# NT_SolarModule_filterfinder.net
KiCad netlist of a schematic drawn in EAGLE
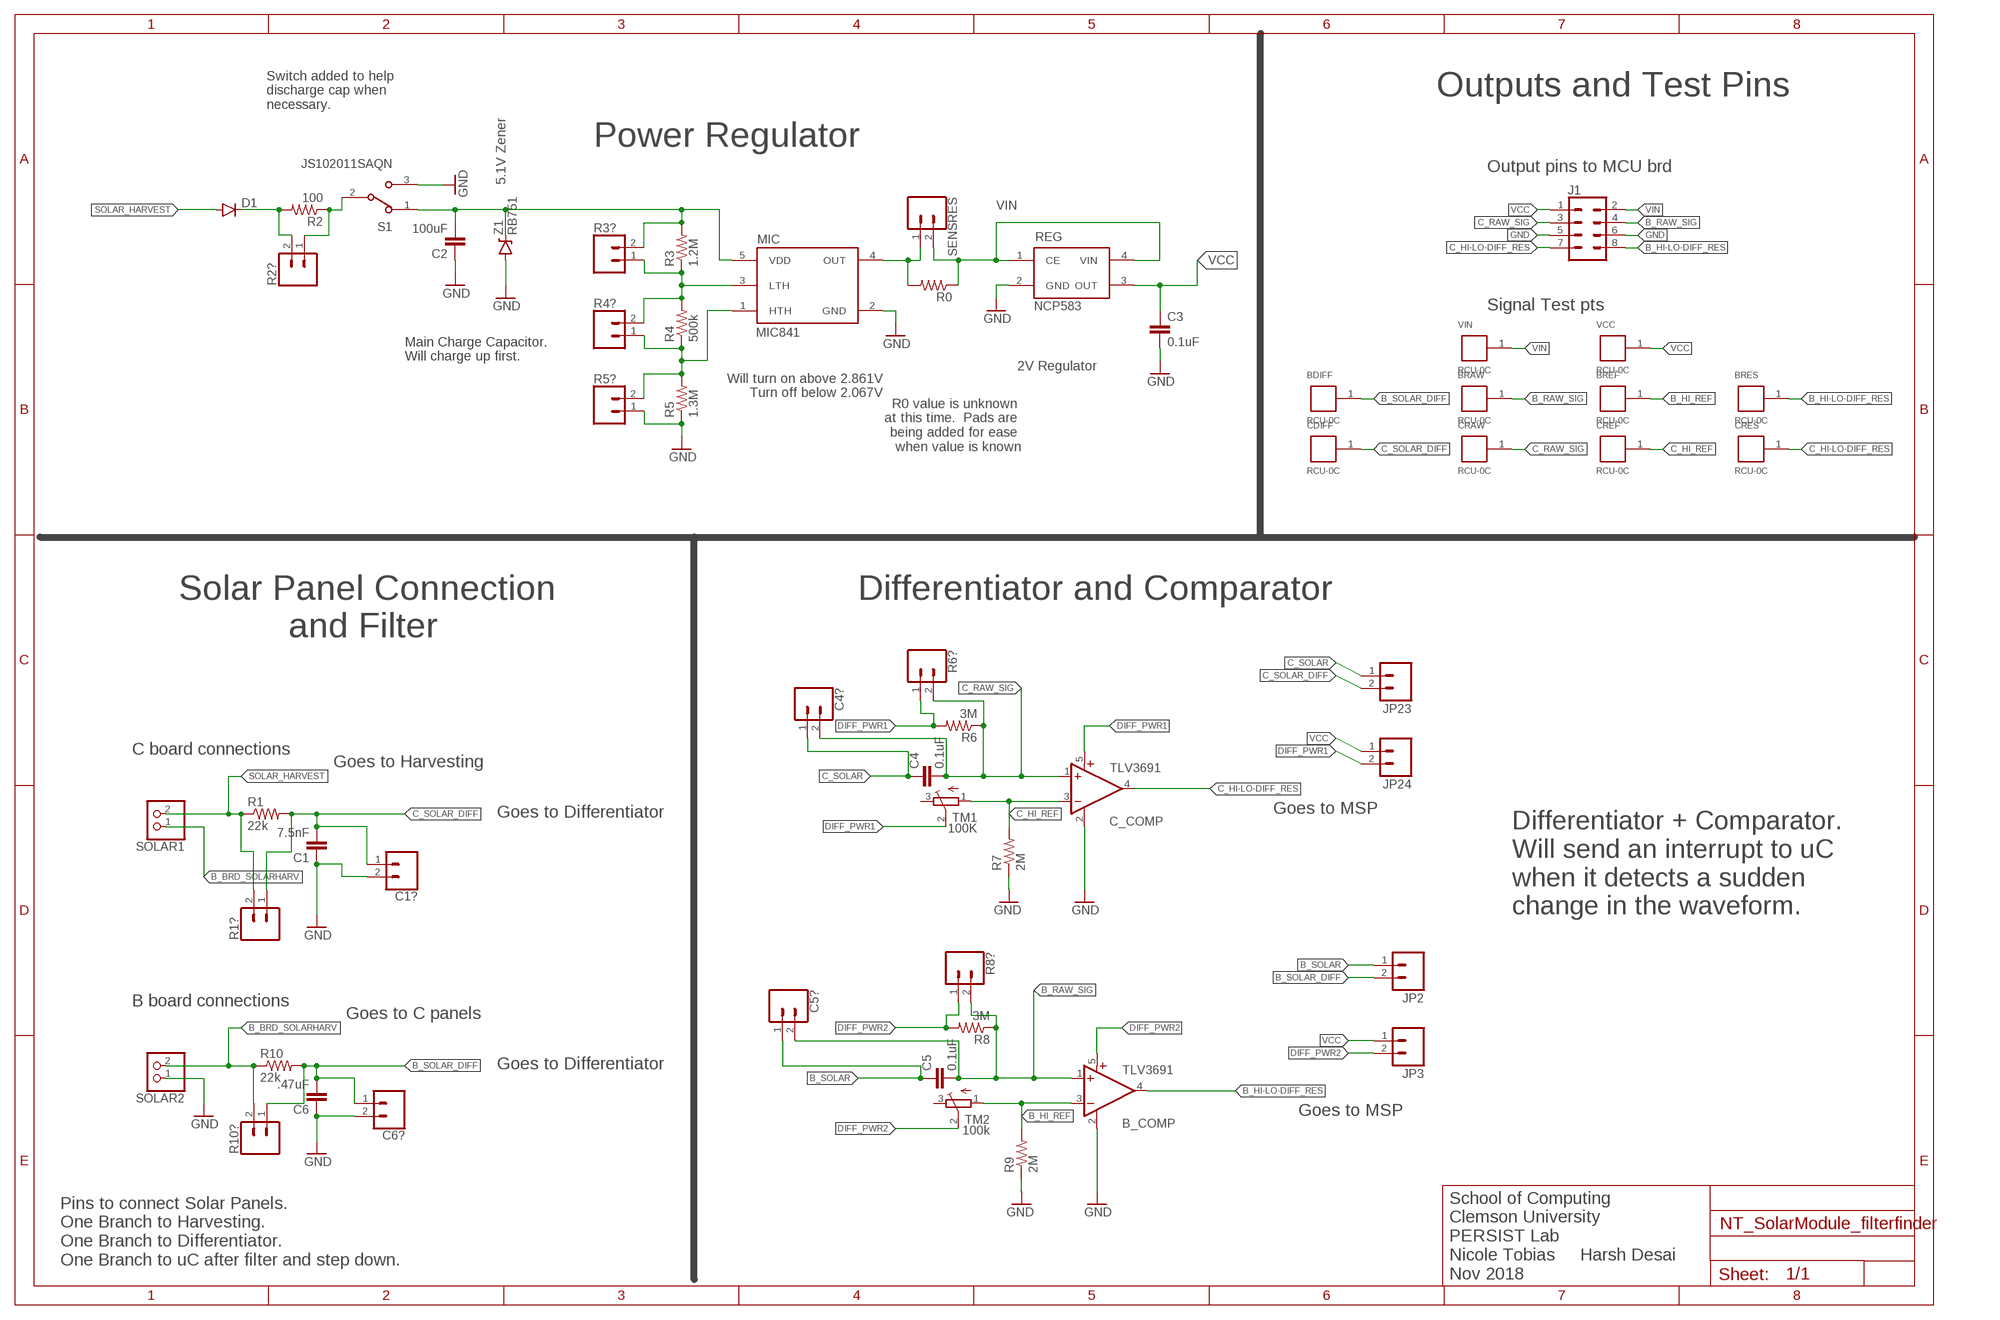
[diagram p0: schematic, sheet 1]

(export (version "E")
  (design (tool "Eeschema 10.0.6"))
  (components
    (comp (ref "BDIFF")
      (value "RCU-0C")
      (footprint "eagle-import:TE_RCU-0C")
      (fields
        (field (name "COMMENT") "RCU-0C _1625854-3_")
        (field (name "MF") "TE Connectivity")
        (field (name "TOLERANCE") "0%")
      )
      (libsource (lib "eagle-import") (part "RCU-0C"))
    )
    (comp (ref "BRAW")
      (value "RCU-0C")
      (footprint "eagle-import:TE_RCU-0C")
      (fields
        (field (name "COMMENT") "RCU-0C _1625854-3_")
        (field (name "MF") "TE Connectivity")
        (field (name "TOLERANCE") "0%")
      )
      (libsource (lib "eagle-import") (part "RCU-0C"))
    )
    (comp (ref "BREF")
      (value "RCU-0C")
      (footprint "eagle-import:TE_RCU-0C")
      (fields
        (field (name "COMMENT") "RCU-0C _1625854-3_")
        (field (name "MF") "TE Connectivity")
        (field (name "TOLERANCE") "0%")
      )
      (libsource (lib "eagle-import") (part "RCU-0C"))
    )
    (comp (ref "BRES")
      (value "RCU-0C")
      (footprint "eagle-import:TE_RCU-0C")
      (fields
        (field (name "COMMENT") "RCU-0C _1625854-3_")
        (field (name "MF") "TE Connectivity")
        (field (name "TOLERANCE") "0%")
      )
      (libsource (lib "eagle-import") (part "RCU-0C"))
    )
    (comp (ref "B_COMP")
      (value "TLV3691")
      (footprint "eagle-import:SC70-5")
      (libsource (lib "eagle-import") (part "TLV3691"))
    )
    (comp (ref "C1")
      (value "7.5nF")
      (footprint "eagle-import:0603-CAP")
      (libsource (lib "eagle-import") (part "CAP0603-CAP"))
    )
    (comp (ref "C1?")
      (value "CONN_02")
      (footprint "eagle-import:1X02")
      (libsource (lib "eagle-import") (part "CONN_02"))
    )
    (comp (ref "C2")
      (value "100uF")
      (footprint "eagle-import:0603-CAP")
      (libsource (lib "eagle-import") (part "CAP0603-CAP"))
    )
    (comp (ref "C3")
      (value "0.1uF")
      (footprint "eagle-import:0603-CAP")
      (libsource (lib "eagle-import") (part "CAP0603-CAP"))
    )
    (comp (ref "C4")
      (value "0.1uF")
      (footprint "eagle-import:0603-CAP")
      (libsource (lib "eagle-import") (part "CAP0603-CAP"))
    )
    (comp (ref "C4?")
      (value "CONN_02")
      (footprint "eagle-import:1X02")
      (libsource (lib "eagle-import") (part "CONN_02"))
    )
    (comp (ref "C5")
      (value "0.1uF")
      (footprint "eagle-import:0603-CAP")
      (libsource (lib "eagle-import") (part "CAP0603-CAP"))
    )
    (comp (ref "C5?")
      (value "CONN_02")
      (footprint "eagle-import:1X02")
      (libsource (lib "eagle-import") (part "CONN_02"))
    )
    (comp (ref "C6")
      (value ".47uF")
      (footprint "eagle-import:0603-CAP")
      (libsource (lib "eagle-import") (part "CAP0603-CAP"))
    )
    (comp (ref "C6?")
      (value "CONN_02")
      (footprint "eagle-import:1X02")
      (libsource (lib "eagle-import") (part "CONN_02"))
    )
    (comp (ref "CDIFF")
      (value "RCU-0C")
      (footprint "eagle-import:TE_RCU-0C")
      (fields
        (field (name "COMMENT") "RCU-0C _1625854-3_")
        (field (name "MF") "TE Connectivity")
        (field (name "TOLERANCE") "0%")
      )
      (libsource (lib "eagle-import") (part "RCU-0C"))
    )
    (comp (ref "CRAW")
      (value "RCU-0C")
      (footprint "eagle-import:TE_RCU-0C")
      (fields
        (field (name "COMMENT") "RCU-0C _1625854-3_")
        (field (name "MF") "TE Connectivity")
        (field (name "TOLERANCE") "0%")
      )
      (libsource (lib "eagle-import") (part "RCU-0C"))
    )
    (comp (ref "CREF")
      (value "RCU-0C")
      (footprint "eagle-import:TE_RCU-0C")
      (fields
        (field (name "COMMENT") "RCU-0C _1625854-3_")
        (field (name "MF") "TE Connectivity")
        (field (name "TOLERANCE") "0%")
      )
      (libsource (lib "eagle-import") (part "RCU-0C"))
    )
    (comp (ref "CRES")
      (value "RCU-0C")
      (footprint "eagle-import:TE_RCU-0C")
      (fields
        (field (name "COMMENT") "RCU-0C _1625854-3_")
        (field (name "MF") "TE Connectivity")
        (field (name "TOLERANCE") "0%")
      )
      (libsource (lib "eagle-import") (part "RCU-0C"))
    )
    (comp (ref "C_COMP")
      (value "TLV3691")
      (footprint "eagle-import:SC70-5")
      (libsource (lib "eagle-import") (part "TLV3691"))
    )
    (comp (ref "D1")
      (value "DIODESOD523")
      (footprint "eagle-import:SOD523")
      (libsource (lib "eagle-import") (part "DIODESOD523"))
    )
    (comp (ref "J1")
      (value "CONN_04X2")
      (footprint "eagle-import:2X4")
      (libsource (lib "eagle-import") (part "CONN_04X2"))
    )
    (comp (ref "JP2")
      (value "M02")
      (footprint "eagle-import:1X02-1.27MM")
      (libsource (lib "eagle-import") (part "M02"))
    )
    (comp (ref "JP3")
      (value "M02")
      (footprint "eagle-import:1X02-1.27MM")
      (libsource (lib "eagle-import") (part "M02"))
    )
    (comp (ref "JP23")
      (value "M02")
      (footprint "eagle-import:1X02-1.27MM")
      (libsource (lib "eagle-import") (part "M02"))
    )
    (comp (ref "JP24")
      (value "M02")
      (footprint "eagle-import:1X02-1.27MM")
      (libsource (lib "eagle-import") (part "M02"))
    )
    (comp (ref "MIC")
      (value "MIC841")
      (footprint "eagle-import:SC70-5")
      (libsource (lib "eagle-import") (part "MIC841"))
    )
    (comp (ref "R0")
      (value "RESISTOR0603")
      (footprint "eagle-import:0603-RES")
      (libsource (lib "eagle-import") (part "RESISTOR0603"))
    )
    (comp (ref "R1")
      (value "22k")
      (footprint "eagle-import:0603-RES")
      (libsource (lib "eagle-import") (part "RESISTOR0603"))
    )
    (comp (ref "R1?")
      (value "CONN_02")
      (footprint "eagle-import:1X02")
      (libsource (lib "eagle-import") (part "CONN_02"))
    )
    (comp (ref "R2")
      (value "100")
      (footprint "eagle-import:0603-RES")
      (libsource (lib "eagle-import") (part "RESISTOR0603"))
    )
    (comp (ref "R2?")
      (value "CONN_02")
      (footprint "eagle-import:1X02")
      (libsource (lib "eagle-import") (part "CONN_02"))
    )
    (comp (ref "R3")
      (value "1.2M")
      (footprint "eagle-import:0603-RES")
      (libsource (lib "eagle-import") (part "RESISTOR0603"))
    )
    (comp (ref "R3?")
      (value "CONN_02")
      (footprint "eagle-import:1X02")
      (libsource (lib "eagle-import") (part "CONN_02"))
    )
    (comp (ref "R4")
      (value "500k")
      (footprint "eagle-import:0603-RES")
      (libsource (lib "eagle-import") (part "RESISTOR0603"))
    )
    (comp (ref "R4?")
      (value "CONN_02")
      (footprint "eagle-import:1X02")
      (libsource (lib "eagle-import") (part "CONN_02"))
    )
    (comp (ref "R5")
      (value "1.3M")
      (footprint "eagle-import:0603-RES")
      (libsource (lib "eagle-import") (part "RESISTOR0603"))
    )
    (comp (ref "R5?")
      (value "CONN_02")
      (footprint "eagle-import:1X02")
      (libsource (lib "eagle-import") (part "CONN_02"))
    )
    (comp (ref "R6")
      (value "3M")
      (footprint "eagle-import:0603-RES")
      (libsource (lib "eagle-import") (part "RESISTOR0603"))
    )
    (comp (ref "R6?")
      (value "CONN_02")
      (footprint "eagle-import:1X02")
      (libsource (lib "eagle-import") (part "CONN_02"))
    )
    (comp (ref "R7")
      (value "2M")
      (footprint "eagle-import:0603-RES")
      (libsource (lib "eagle-import") (part "RESISTOR0603"))
    )
    (comp (ref "R8")
      (value "3M")
      (footprint "eagle-import:0603-RES")
      (libsource (lib "eagle-import") (part "RESISTOR0603"))
    )
    (comp (ref "R8?")
      (value "CONN_02")
      (footprint "eagle-import:1X02")
      (libsource (lib "eagle-import") (part "CONN_02"))
    )
    (comp (ref "R9")
      (value "2M")
      (footprint "eagle-import:0603-RES")
      (libsource (lib "eagle-import") (part "RESISTOR0603"))
    )
    (comp (ref "R10")
      (value "22k")
      (footprint "eagle-import:0603-RES")
      (libsource (lib "eagle-import") (part "RESISTOR0603"))
    )
    (comp (ref "R10?")
      (value "CONN_02")
      (footprint "eagle-import:1X02")
      (libsource (lib "eagle-import") (part "CONN_02"))
    )
    (comp (ref "REG")
      (value "NCP583")
      (footprint "eagle-import:SC82-AB_1PRIMARY")
      (libsource (lib "eagle-import") (part "NCP583"))
    )
    (comp (ref "S1")
      (value "JS102011SAQN")
      (footprint "eagle-import:SW_JS102011SAQN")
      (fields (field (name "MF") "C&K Components"))
      (libsource (lib "eagle-import") (part "JS102011SAQN"))
    )
    (comp (ref "SENSRES")
      (value "CONN_02")
      (footprint "eagle-import:1X02")
      (libsource (lib "eagle-import") (part "CONN_02"))
    )
    (comp (ref "SOLAR1")
      (value "PINHD-1X2")
      (footprint "eagle-import:1X02")
      (libsource (lib "eagle-import") (part "PINHD-1X2"))
    )
    (comp (ref "SOLAR2")
      (value "PINHD-1X2")
      (footprint "eagle-import:1X02")
      (libsource (lib "eagle-import") (part "PINHD-1X2"))
    )
    (comp (ref "TM1")
      (value "100K")
      (footprint "eagle-import:TC33X")
      (libsource (lib "eagle-import") (part "TRIMPOTTC33X"))
    )
    (comp (ref "TM2")
      (value "100k")
      (footprint "eagle-import:TC33X")
      (libsource (lib "eagle-import") (part "TRIMPOTTC33X"))
    )
    (comp (ref "VCC")
      (value "RCU-0C")
      (footprint "eagle-import:TE_RCU-0C")
      (fields
        (field (name "COMMENT") "RCU-0C _1625854-3_")
        (field (name "MF") "TE Connectivity")
        (field (name "TOLERANCE") "0%")
      )
      (libsource (lib "eagle-import") (part "RCU-0C"))
    )
    (comp (ref "VIN")
      (value "RCU-0C")
      (footprint "eagle-import:TE_RCU-0C")
      (fields
        (field (name "COMMENT") "RCU-0C _1625854-3_")
        (field (name "MF") "TE Connectivity")
        (field (name "TOLERANCE") "0%")
      )
      (libsource (lib "eagle-import") (part "RCU-0C"))
    )
    (comp (ref "Z1")
      (value "RB751")
      (footprint "eagle-import:SOD-523")
      (libsource (lib "eagle-import") (part "DIODE-ZENER"))
    )
  )
  (nets
    (net (code "1") (name "B_BRD_SOLARHARV") (class "Default")
      (node (ref "R10") (pin "1") (pinfunction "1_1") (pintype "passive"))
      (node (ref "R10?") (pin "2") (pinfunction "2_2") (pintype "passive"))
      (node (ref "SOLAR1") (pin "1") (pinfunction "1_1") (pintype "passive"))
      (node (ref "SOLAR2") (pin "2") (pinfunction "2_2") (pintype "passive"))
    )
    (net (code "2") (name "B_HI-LO-DIFF_RES") (class "Default")
      (node (ref "BRES") (pin "1") (pinfunction "1_1") (pintype "passive"))
      (node (ref "B_COMP") (pin "4") (pinfunction "OUT_4") (pintype "output"))
      (node (ref "J1") (pin "8") (pinfunction "8_8") (pintype "passive"))
    )
    (net (code "3") (name "B_HI_REF") (class "Default")
      (node (ref "BREF") (pin "1") (pinfunction "1_1") (pintype "passive"))
      (node (ref "B_COMP") (pin "3") (pinfunction "-IN_3") (pintype "input"))
      (node (ref "R9") (pin "2") (pinfunction "2_2") (pintype "passive"))
      (node (ref "TM2") (pin "1") (pinfunction "A_1") (pintype "passive"))
    )
    (net (code "4") (name "B_RAW_SIG") (class "Default")
      (node (ref "BRAW") (pin "1") (pinfunction "1_1") (pintype "passive"))
      (node (ref "B_COMP") (pin "1") (pinfunction "+IN_1") (pintype "input"))
      (node (ref "C5") (pin "2") (pinfunction "2_2") (pintype "passive"))
      (node (ref "C5?") (pin "2") (pinfunction "2_2") (pintype "passive"))
      (node (ref "J1") (pin "4") (pinfunction "4_4") (pintype "passive"))
      (node (ref "R8") (pin "1") (pinfunction "1_1") (pintype "passive"))
      (node (ref "R8?") (pin "2") (pinfunction "2_2") (pintype "passive"))
    )
    (net (code "5") (name "B_SOLAR") (class "Default")
      (node (ref "C5") (pin "1") (pinfunction "1_1") (pintype "passive"))
      (node (ref "C5?") (pin "1") (pinfunction "1_1") (pintype "passive"))
      (node (ref "JP2") (pin "1") (pinfunction "1_1") (pintype "passive"))
    )
    (net (code "6") (name "B_SOLAR_DIFF") (class "Default")
      (node (ref "BDIFF") (pin "1") (pinfunction "1_1") (pintype "passive"))
      (node (ref "C6") (pin "2") (pinfunction "2_2") (pintype "passive"))
      (node (ref "C6?") (pin "1") (pinfunction "1_1") (pintype "passive"))
      (node (ref "JP2") (pin "2") (pinfunction "2_2") (pintype "passive"))
      (node (ref "R10") (pin "2") (pinfunction "2_2") (pintype "passive"))
      (node (ref "R10?") (pin "1") (pinfunction "1_1") (pintype "passive"))
    )
    (net (code "7") (name "C_HI-LO-DIFF_RES") (class "Default")
      (node (ref "CRES") (pin "1") (pinfunction "1_1") (pintype "passive"))
      (node (ref "C_COMP") (pin "4") (pinfunction "OUT_4") (pintype "output"))
      (node (ref "J1") (pin "7") (pinfunction "7_7") (pintype "passive"))
    )
    (net (code "8") (name "C_HI_REF") (class "Default")
      (node (ref "CREF") (pin "1") (pinfunction "1_1") (pintype "passive"))
      (node (ref "C_COMP") (pin "3") (pinfunction "-IN_3") (pintype "input"))
      (node (ref "R7") (pin "2") (pinfunction "2_2") (pintype "passive"))
      (node (ref "TM1") (pin "1") (pinfunction "A_1") (pintype "passive"))
    )
    (net (code "9") (name "C_RAW_SIG") (class "Default")
      (node (ref "C4") (pin "2") (pinfunction "2_2") (pintype "passive"))
      (node (ref "C4?") (pin "2") (pinfunction "2_2") (pintype "passive"))
      (node (ref "CRAW") (pin "1") (pinfunction "1_1") (pintype "passive"))
      (node (ref "C_COMP") (pin "1") (pinfunction "+IN_1") (pintype "input"))
      (node (ref "J1") (pin "3") (pinfunction "3_3") (pintype "passive"))
      (node (ref "R6") (pin "1") (pinfunction "1_1") (pintype "passive"))
      (node (ref "R6?") (pin "2") (pinfunction "2_2") (pintype "passive"))
    )
    (net (code "10") (name "C_SOLAR") (class "Default")
      (node (ref "C4") (pin "1") (pinfunction "1_1") (pintype "passive"))
      (node (ref "C4?") (pin "1") (pinfunction "1_1") (pintype "passive"))
      (node (ref "JP23") (pin "1") (pinfunction "1_1") (pintype "passive"))
    )
    (net (code "11") (name "C_SOLAR_DIFF") (class "Default")
      (node (ref "C1") (pin "2") (pinfunction "2_2") (pintype "passive"))
      (node (ref "C1?") (pin "1") (pinfunction "1_1") (pintype "passive"))
      (node (ref "CDIFF") (pin "1") (pinfunction "1_1") (pintype "passive"))
      (node (ref "JP23") (pin "2") (pinfunction "2_2") (pintype "passive"))
      (node (ref "R1") (pin "2") (pinfunction "2_2") (pintype "passive"))
      (node (ref "R1?") (pin "1") (pinfunction "1_1") (pintype "passive"))
    )
    (net (code "12") (name "DIFF_PWR1") (class "Default")
      (node (ref "C_COMP") (pin "5") (pinfunction "V+_5") (pintype "power_in"))
      (node (ref "JP24") (pin "2") (pinfunction "2_2") (pintype "passive"))
      (node (ref "R6") (pin "2") (pinfunction "2_2") (pintype "passive"))
      (node (ref "R6?") (pin "1") (pinfunction "1_1") (pintype "passive"))
      (node (ref "TM1") (pin "2") (pinfunction "S_2") (pintype "passive"))
    )
    (net (code "13") (name "DIFF_PWR2") (class "Default")
      (node (ref "B_COMP") (pin "5") (pinfunction "V+_5") (pintype "power_in"))
      (node (ref "JP3") (pin "2") (pinfunction "2_2") (pintype "passive"))
      (node (ref "R8") (pin "2") (pinfunction "2_2") (pintype "passive"))
      (node (ref "R8?") (pin "1") (pinfunction "1_1") (pintype "passive"))
      (node (ref "TM2") (pin "2") (pinfunction "S_2") (pintype "passive"))
    )
    (net (code "14") (name "GND") (class "Default")
      (node (ref "B_COMP") (pin "2") (pinfunction "GND_2") (pintype "power_in"))
      (node (ref "C1") (pin "1") (pinfunction "1_1") (pintype "passive"))
      (node (ref "C1?") (pin "2") (pinfunction "2_2") (pintype "passive"))
      (node (ref "C2") (pin "1") (pinfunction "1_1") (pintype "passive"))
      (node (ref "C3") (pin "2") (pinfunction "2_2") (pintype "passive"))
      (node (ref "C6") (pin "1") (pinfunction "1_1") (pintype "passive"))
      (node (ref "C6?") (pin "2") (pinfunction "2_2") (pintype "passive"))
      (node (ref "C_COMP") (pin "2") (pinfunction "GND_2") (pintype "power_in"))
      (node (ref "J1") (pin "5") (pinfunction "5_5") (pintype "passive"))
      (node (ref "J1") (pin "6") (pinfunction "6_6") (pintype "passive"))
      (node (ref "MIC") (pin "2") (pinfunction "GND_2") (pintype "bidirectional"))
      (node (ref "R5") (pin "1") (pinfunction "1_1") (pintype "passive"))
      (node (ref "R5?") (pin "1") (pinfunction "1_1") (pintype "passive"))
      (node (ref "R7") (pin "1") (pinfunction "1_1") (pintype "passive"))
      (node (ref "R9") (pin "1") (pinfunction "1_1") (pintype "passive"))
      (node (ref "REG") (pin "2") (pinfunction "GND_2") (pintype "bidirectional"))
      (node (ref "S1") (pin "3") (pinfunction "3_3") (pintype "passive"))
      (node (ref "SOLAR2") (pin "1") (pinfunction "1_1") (pintype "passive"))
      (node (ref "Z1") (pin "ANODE") (pinfunction "A_ANODE") (pintype "passive"))
    )
    (net (code "15") (name "Net-(D1-PadC)") (class "Default")
      (node (ref "D1") (pin "C") (pinfunction "C_C") (pintype "passive"))
      (node (ref "R2") (pin "2") (pinfunction "2_2") (pintype "passive"))
      (node (ref "R2?") (pin "2") (pinfunction "2_2") (pintype "passive"))
    )
    (net (code "16") (name "Net-(MIC-HTH)") (class "Default")
      (node (ref "MIC") (pin "1") (pinfunction "HTH_1") (pintype "bidirectional"))
      (node (ref "R4") (pin "1") (pinfunction "1_1") (pintype "passive"))
      (node (ref "R4?") (pin "1") (pinfunction "1_1") (pintype "passive"))
      (node (ref "R5") (pin "2") (pinfunction "2_2") (pintype "passive"))
      (node (ref "R5?") (pin "2") (pinfunction "2_2") (pintype "passive"))
    )
    (net (code "17") (name "Net-(MIC-LTH)") (class "Default")
      (node (ref "MIC") (pin "3") (pinfunction "LTH_3") (pintype "bidirectional"))
      (node (ref "R3") (pin "1") (pinfunction "1_1") (pintype "passive"))
      (node (ref "R3?") (pin "1") (pinfunction "1_1") (pintype "passive"))
      (node (ref "R4") (pin "2") (pinfunction "2_2") (pintype "passive"))
      (node (ref "R4?") (pin "2") (pinfunction "2_2") (pintype "passive"))
    )
    (net (code "18") (name "Net-(MIC-OUT)") (class "Default")
      (node (ref "MIC") (pin "4") (pinfunction "OUT_4") (pintype "bidirectional"))
      (node (ref "R0") (pin "2") (pinfunction "2_2") (pintype "passive"))
      (node (ref "SENSRES") (pin "1") (pinfunction "1_1") (pintype "passive"))
    )
    (net (code "19") (name "Net-(MIC-VDD)") (class "Default")
      (node (ref "C2") (pin "2") (pinfunction "2_2") (pintype "passive"))
      (node (ref "MIC") (pin "5") (pinfunction "VDD_5") (pintype "bidirectional"))
      (node (ref "R3") (pin "2") (pinfunction "2_2") (pintype "passive"))
      (node (ref "R3?") (pin "2") (pinfunction "2_2") (pintype "passive"))
      (node (ref "S1") (pin "1") (pinfunction "1_1") (pintype "passive"))
      (node (ref "Z1") (pin "CATHODE") (pinfunction "C_CATHODE") (pintype "passive"))
    )
    (net (code "20") (name "Net-(R2-Pad1)") (class "Default")
      (node (ref "R2") (pin "1") (pinfunction "1_1") (pintype "passive"))
      (node (ref "R2?") (pin "1") (pinfunction "1_1") (pintype "passive"))
      (node (ref "S1") (pin "2") (pinfunction "2_2") (pintype "passive"))
    )
    (net (code "21") (name "SOLAR_HARVEST") (class "Default")
      (node (ref "D1") (pin "A") (pinfunction "A_A") (pintype "passive"))
      (node (ref "R1") (pin "1") (pinfunction "1_1") (pintype "passive"))
      (node (ref "R1?") (pin "2") (pinfunction "2_2") (pintype "passive"))
      (node (ref "SOLAR1") (pin "2") (pinfunction "2_2") (pintype "passive"))
    )
    (net (code "22") (name "VCC") (class "Default")
      (node (ref "C3") (pin "1") (pinfunction "1_1") (pintype "passive"))
      (node (ref "J1") (pin "1") (pinfunction "1_1") (pintype "passive"))
      (node (ref "JP24") (pin "1") (pinfunction "1_1") (pintype "passive"))
      (node (ref "JP3") (pin "1") (pinfunction "1_1") (pintype "passive"))
      (node (ref "REG") (pin "3") (pinfunction "OUT_3") (pintype "bidirectional"))
      (node (ref "VCC") (pin "1") (pinfunction "1_1") (pintype "passive"))
    )
    (net (code "23") (name "VIN") (class "Default")
      (node (ref "J1") (pin "2") (pinfunction "2_2") (pintype "passive"))
      (node (ref "R0") (pin "1") (pinfunction "1_1") (pintype "passive"))
      (node (ref "REG") (pin "1") (pinfunction "CE_1") (pintype "bidirectional"))
      (node (ref "REG") (pin "4") (pinfunction "VIN_4") (pintype "bidirectional"))
      (node (ref "SENSRES") (pin "2") (pinfunction "2_2") (pintype "passive"))
      (node (ref "VIN") (pin "1") (pinfunction "1_1") (pintype "passive"))
    )
    (net (code "24") (name "unconnected-(TM1-E-Pad3)") (class "Default")
      (node (ref "TM1") (pin "3") (pinfunction "E_3") (pintype "passive"))
    )
    (net (code "25") (name "unconnected-(TM2-E-Pad3)") (class "Default")
      (node (ref "TM2") (pin "3") (pinfunction "E_3") (pintype "passive"))
    )
  )
)
